# B01_IchigojamCap-Y_v1_0.net
KiCad netlist of a schematic drawn in EAGLE
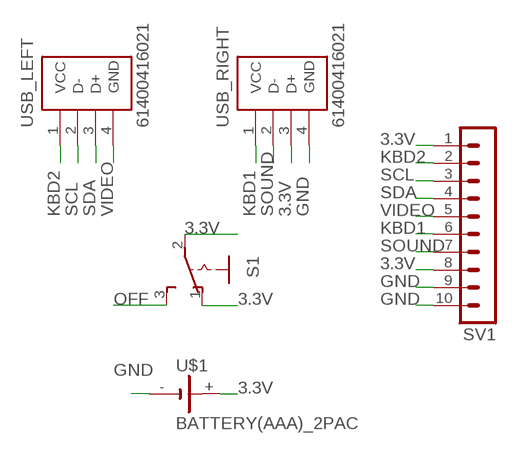
[diagram p0: schematic, sheet 1]

(export (version "E")
  (design (tool "Eeschema 10.0.6"))
  (components
    (comp (ref "S1")
      (value "255SB")
      (footprint "eagle-import:255SB")
      (libsource (lib "eagle-import") (part "255SB"))
    )
    (comp (ref "SV1")
      (value "MA10-1")
      (footprint "eagle-import:MA10-1")
      (libsource (lib "eagle-import") (part "MA10-1"))
    )
    (comp (ref "U$1")
      (value "BATTERY(AAA)_2PAC")
      (footprint "eagle-import:BATTERY_HOLDER")
      (libsource (lib "eagle-import") (part "BATTERY(AAA)_2PAC"))
    )
    (comp (ref "USB_LEFT")
      (value "61400416021")
      (footprint "eagle-import:61400416021")
      (libsource (lib "eagle-import") (part "61400416021"))
    )
    (comp (ref "USB_RIGHT")
      (value "61400416021")
      (footprint "eagle-import:61400416021")
      (libsource (lib "eagle-import") (part "61400416021"))
    )
  )
  (nets
    (net (code "1") (name "/3.3V") (class "Default")
      (node (ref "S1") (pin "1") (pinfunction "O_1") (pintype "passive"))
      (node (ref "S1") (pin "2") (pinfunction "P_2") (pintype "passive"))
      (node (ref "SV1") (pin "1") (pinfunction "1_1") (pintype "passive"))
      (node (ref "SV1") (pin "8") (pinfunction "8_8") (pintype "passive"))
      (node (ref "U$1") (pin "+") (pinfunction "+_+") (pintype "passive"))
      (node (ref "USB_RIGHT") (pin "3") (pinfunction "D+_3") (pintype "passive"))
    )
    (net (code "2") (name "/GND") (class "Default")
      (node (ref "SV1") (pin "10") (pinfunction "10_10") (pintype "passive"))
      (node (ref "SV1") (pin "9") (pinfunction "9_9") (pintype "passive"))
      (node (ref "U$1") (pin "-") (pinfunction "-_-") (pintype "passive"))
      (node (ref "USB_RIGHT") (pin "4") (pinfunction "GND_4") (pintype "passive"))
    )
    (net (code "3") (name "/KBD1") (class "Default")
      (node (ref "SV1") (pin "6") (pinfunction "6_6") (pintype "passive"))
      (node (ref "USB_RIGHT") (pin "1") (pinfunction "VCC_1") (pintype "passive"))
    )
    (net (code "4") (name "/KBD2") (class "Default")
      (node (ref "SV1") (pin "2") (pinfunction "2_2") (pintype "passive"))
      (node (ref "USB_LEFT") (pin "1") (pinfunction "VCC_1") (pintype "passive"))
    )
    (net (code "5") (name "/OFF") (class "Default")
      (node (ref "S1") (pin "3") (pinfunction "S_3") (pintype "passive"))
    )
    (net (code "6") (name "/SCL") (class "Default")
      (node (ref "SV1") (pin "3") (pinfunction "3_3") (pintype "passive"))
      (node (ref "USB_LEFT") (pin "2") (pinfunction "D-_2") (pintype "passive"))
    )
    (net (code "7") (name "/SDA") (class "Default")
      (node (ref "SV1") (pin "4") (pinfunction "4_4") (pintype "passive"))
      (node (ref "USB_LEFT") (pin "3") (pinfunction "D+_3") (pintype "passive"))
    )
    (net (code "8") (name "/SOUND") (class "Default")
      (node (ref "SV1") (pin "7") (pinfunction "7_7") (pintype "passive"))
      (node (ref "USB_RIGHT") (pin "2") (pinfunction "D-_2") (pintype "passive"))
    )
    (net (code "9") (name "/VIDEO") (class "Default")
      (node (ref "SV1") (pin "5") (pinfunction "5_5") (pintype "passive"))
      (node (ref "USB_LEFT") (pin "4") (pinfunction "GND_4") (pintype "passive"))
    )
  )
)
